# SUPPORT.net
KiCad netlist of a schematic drawn in Altium Designer
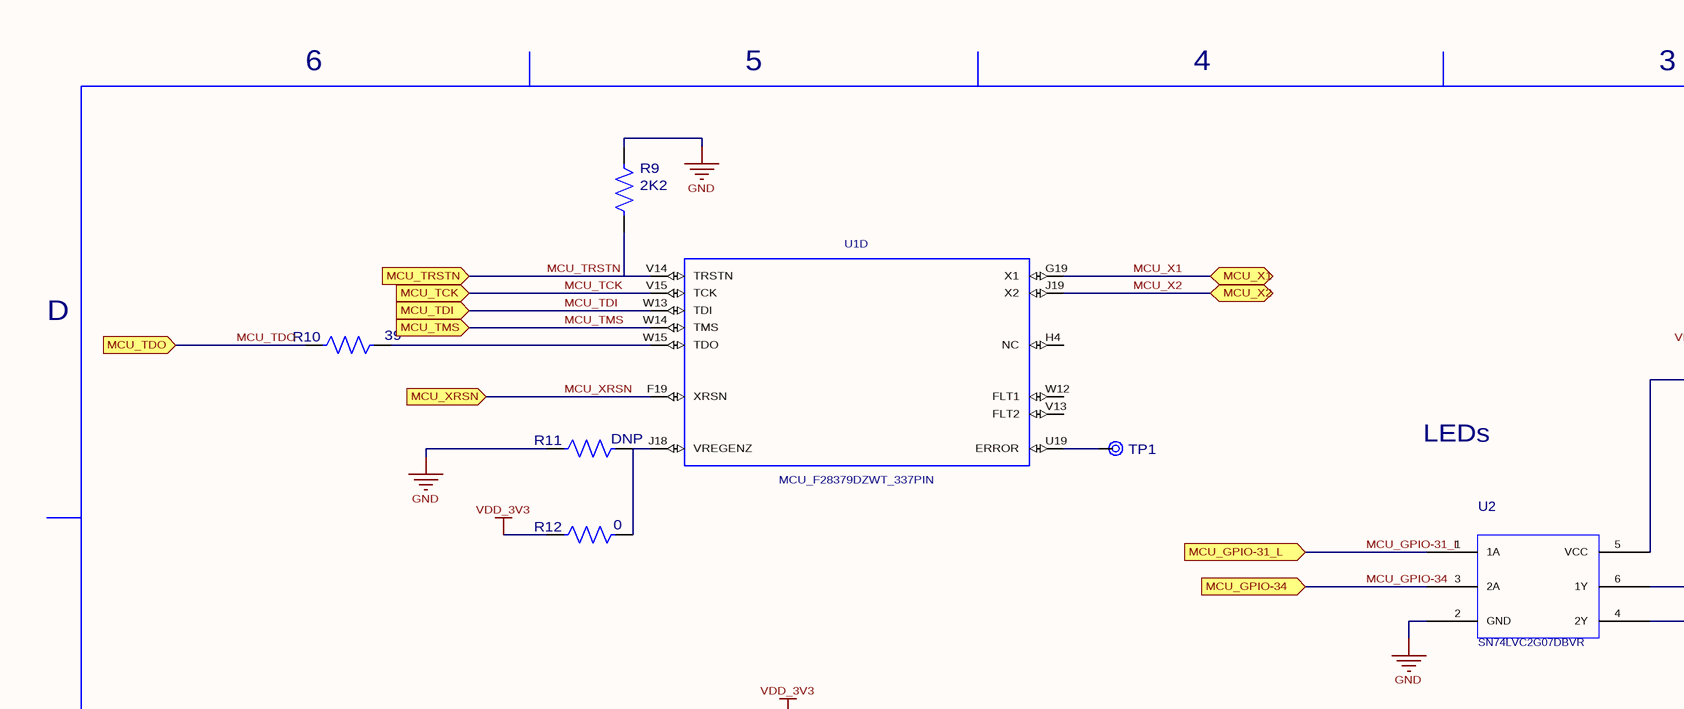
[diagram p0: SUPPORT.SchDoc, top left]
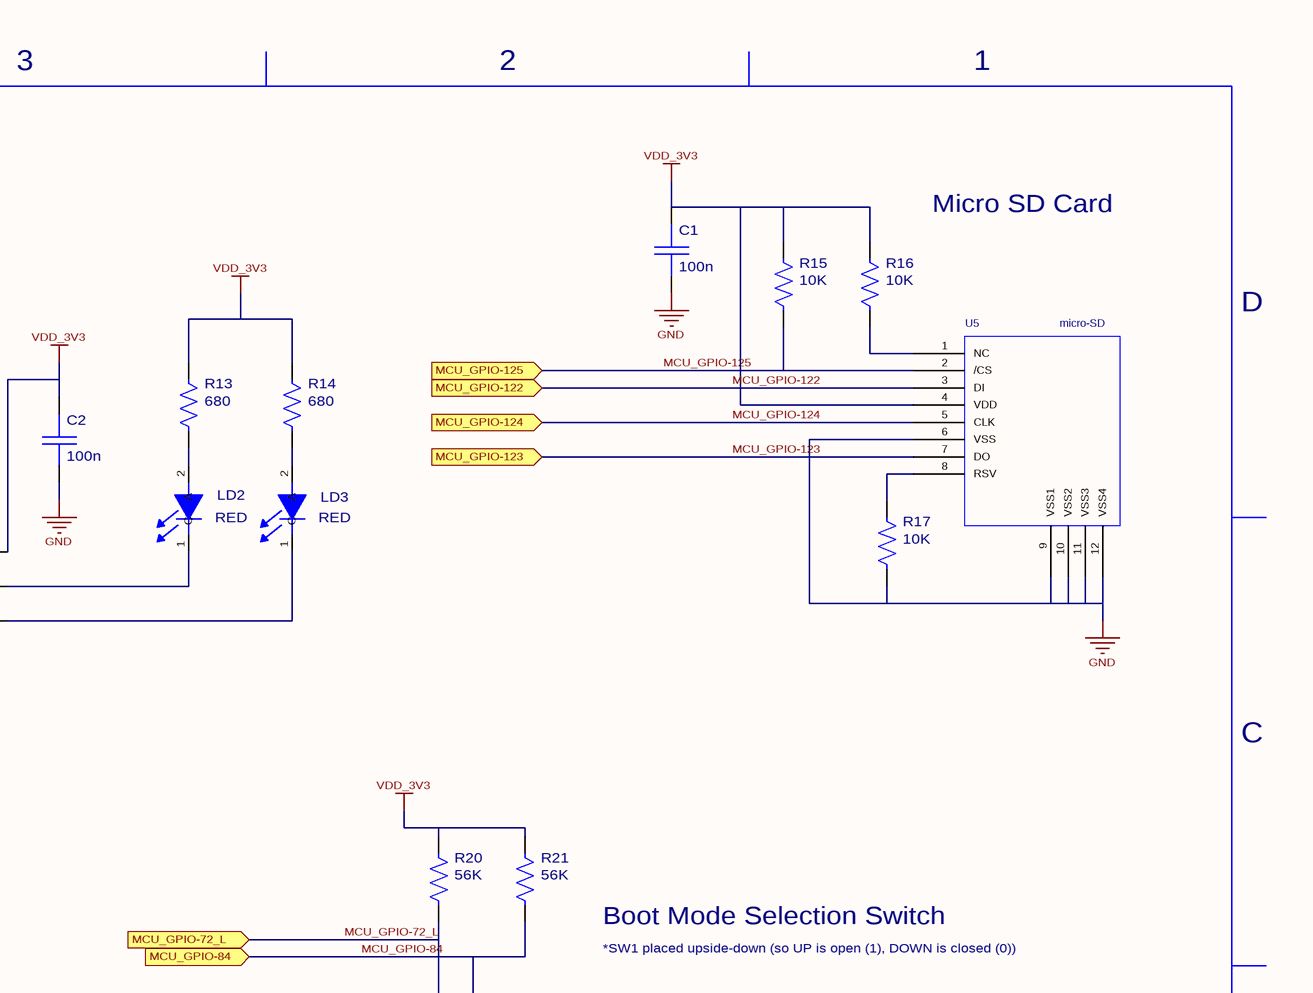
[diagram p1: SUPPORT.SchDoc, top right]
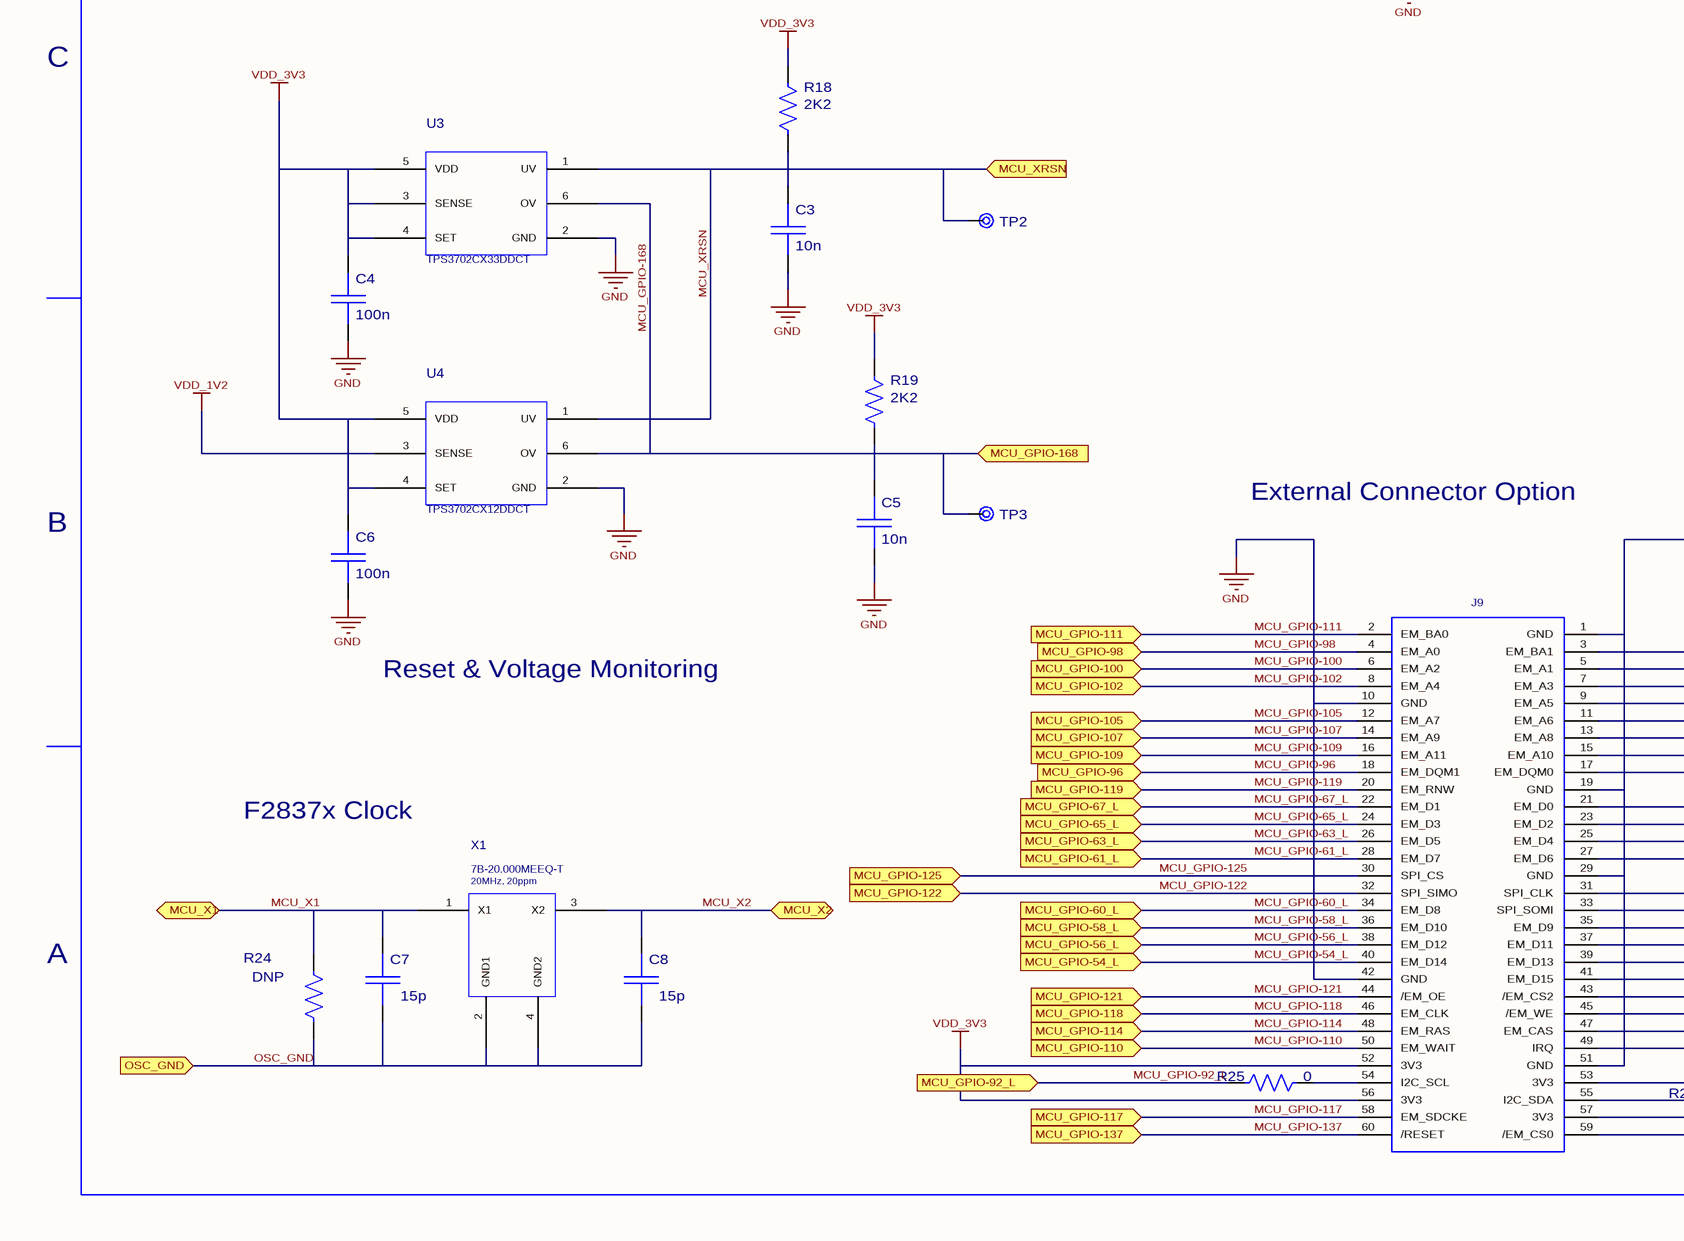
[diagram p2: SUPPORT.SchDoc, bottom left]
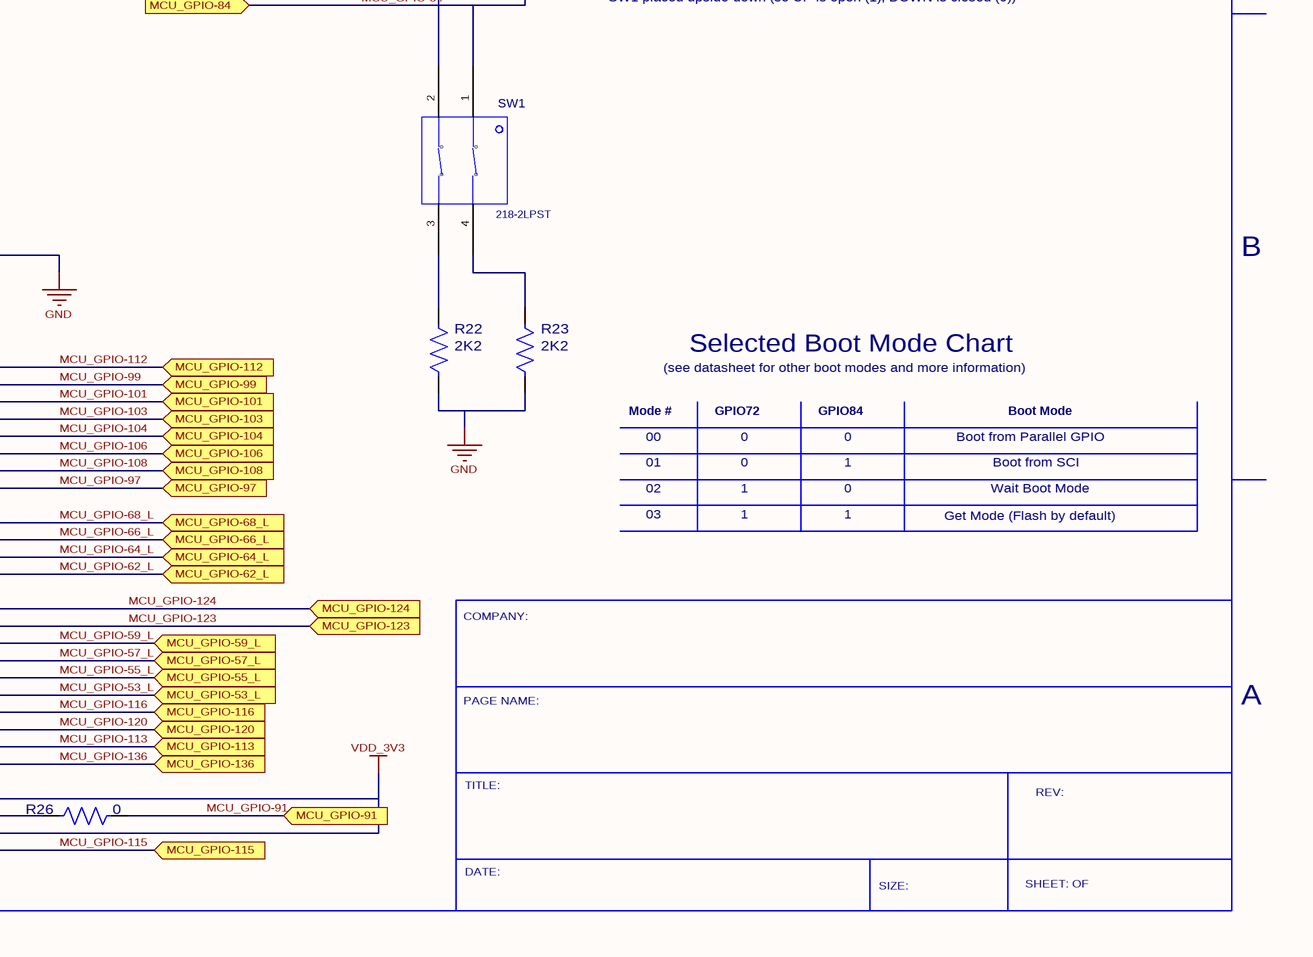
[diagram p3: SUPPORT.SchDoc, bottom right]

(export (version "E")
  (design (tool "Eeschema 10.0.6"))
  (components
    (comp (ref "C1")
      (value "100n")
      (footprint "C0402")
      (description "CAP CER 16V 10% X7R 0402")
      (fields (field (name "Comment") "C0402_16V_X7R"))
      (libsource (lib "*") (part "C0402_16V_X7R"))
    )
    (comp (ref "C2")
      (value "100n")
      (footprint "C0402")
      (description "CAP CER 16V 10% X7R 0402")
      (fields (field (name "Comment") "C0402_16V_X7R"))
      (libsource (lib "*") (part "C0402_16V_X7R"))
    )
    (comp (ref "C3")
      (value "10n")
      (footprint "C0402")
      (description "CAP CER 16V 10% X7R 0402")
      (fields (field (name "Comment") "C0402_16V_X7R"))
      (libsource (lib "*") (part "C0402_16V_X7R"))
    )
    (comp (ref "C4")
      (value "100n")
      (footprint "C0402")
      (description "CAP CER 16V 10% X7R 0402")
      (fields (field (name "Comment") "C0402_16V_X7R"))
      (libsource (lib "*") (part "C0402_16V_X7R"))
    )
    (comp (ref "C5")
      (value "10n")
      (footprint "C0402")
      (description "CAP CER 16V 10% X7R 0402")
      (fields (field (name "Comment") "C0402_16V_X7R"))
      (libsource (lib "*") (part "C0402_16V_X7R"))
    )
    (comp (ref "C6")
      (value "100n")
      (footprint "C0402")
      (description "CAP CER 16V 10% X7R 0402")
      (fields (field (name "Comment") "C0402_16V_X7R"))
      (libsource (lib "*") (part "C0402_16V_X7R"))
    )
    (comp (ref "C7")
      (value "15p")
      (footprint "C0402")
      (description "CAP CER 50V NP0 0402")
      (fields (field (name "Comment") "C0402_50V_NP0"))
      (libsource (lib "*") (part "C0402_50V_NP0"))
    )
    (comp (ref "C8")
      (value "15p")
      (footprint "C0402")
      (description "CAP CER 50V NP0 0402")
      (fields (field (name "Comment") "C0402_50V_NP0"))
      (libsource (lib "*") (part "C0402_50V_NP0"))
    )
    (comp (ref "J9")
      (value "CONN_DF40C_CCARDIF_EMIFANDSPI")
      (footprint "DF40C-60DP-0.4V")
      (description "60pin connector - SMT, Hirose DF40C-60DP-0.4V(51)")
      (fields (field (name "MANUFACTURER") "Hirose") (field (name "PART NUMBER") "DF40C-60DP-0.4V(51)"))
      (libsource (lib "*") (part "CONN_DF40C_CCARDIF_EMIFANDSPI"))
    )
    (comp (ref "LD2")
      (value "RED")
      (footprint "LED0805")
      (description "LED RED 0805 SMD, Diffused, 647nm")
      (fields (field (name "Comment") "LED0805_RED"))
      (libsource (lib "*") (part "LED0805_RED"))
    )
    (comp (ref "LD3")
      (value "RED")
      (footprint "LED0805")
      (description "LED RED 0805 SMD, Diffused, 647nm")
      (fields (field (name "Comment") "LED0805_RED"))
      (libsource (lib "*") (part "LED0805_RED"))
    )
    (comp (ref "R9")
      (value "2K2")
      (footprint "R0402")
      (description "RES 1/16W 5% 0402 SMD")
      (fields (field (name "Comment") "R0402_5%"))
      (libsource (lib "*") (part "R0402_5%"))
    )
    (comp (ref "R10")
      (value "39")
      (footprint "R0402")
      (description "RES 1/16W 5% 0402 SMD")
      (fields (field (name "Comment") "R0402_5%"))
      (libsource (lib "*") (part "R0402_5%"))
    )
    (comp (ref "R11")
      (value "DNP")
      (footprint "R0402")
      (description "RES 1/16W 5% 0402 SMD")
      (fields (field (name "Comment") "R0402_5%"))
      (libsource (lib "*") (part "R0402_5%"))
    )
    (comp (ref "R12")
      (value "0")
      (footprint "R0402")
      (description "RES 1/16W 5% 0402 SMD")
      (fields (field (name "Comment") "R0402_5%"))
      (libsource (lib "*") (part "R0402_5%"))
    )
    (comp (ref "R13")
      (value "680")
      (footprint "R0402")
      (description "RES 1/16W 5% 0402 SMD")
      (fields (field (name "Comment") "R0402_5%"))
      (libsource (lib "*") (part "R0402_5%"))
    )
    (comp (ref "R14")
      (value "680")
      (footprint "R0402")
      (description "RES 1/16W 5% 0402 SMD")
      (fields (field (name "Comment") "R0402_5%"))
      (libsource (lib "*") (part "R0402_5%"))
    )
    (comp (ref "R15")
      (value "10K")
      (footprint "R0402")
      (description "RES 1/16W 5% 0402 SMD")
      (fields (field (name "Comment") "R0402_5%"))
      (libsource (lib "*") (part "R0402_5%"))
    )
    (comp (ref "R16")
      (value "10K")
      (footprint "R0402")
      (description "RES 1/16W 5% 0402 SMD")
      (fields (field (name "Comment") "R0402_5%"))
      (libsource (lib "*") (part "R0402_5%"))
    )
    (comp (ref "R17")
      (value "10K")
      (footprint "R0402")
      (description "RES 1/16W 5% 0402 SMD")
      (fields (field (name "Comment") "R0402_5%"))
      (libsource (lib "*") (part "R0402_5%"))
    )
    (comp (ref "R18")
      (value "2K2")
      (footprint "R0402")
      (description "RES 1/16W 5% 0402 SMD")
      (fields (field (name "Comment") "R0402_5%"))
      (libsource (lib "*") (part "R0402_5%"))
    )
    (comp (ref "R19")
      (value "2K2")
      (footprint "R0603")
      (description "RES 1/10W 1% 0603 SMD")
      (fields (field (name "Comment") "R0603_1%"))
      (libsource (lib "*") (part "R0603_1%"))
    )
    (comp (ref "R20")
      (value "56K")
      (footprint "R0402")
      (description "RES 1/16W 5% 0402 SMD")
      (fields (field (name "Comment") "R0402_5%"))
      (libsource (lib "*") (part "R0402_5%"))
    )
    (comp (ref "R21")
      (value "56K")
      (footprint "R0402")
      (description "RES 1/16W 5% 0402 SMD")
      (fields (field (name "Comment") "R0402_5%"))
      (libsource (lib "*") (part "R0402_5%"))
    )
    (comp (ref "R22")
      (value "2K2")
      (footprint "R0402")
      (description "RES 1/16W 5% 0402 SMD")
      (fields (field (name "Comment") "R0402_5%"))
      (libsource (lib "*") (part "R0402_5%"))
    )
    (comp (ref "R23")
      (value "2K2")
      (footprint "R0402")
      (description "RES 1/16W 5% 0402 SMD")
      (fields (field (name "Comment") "R0402_5%"))
      (libsource (lib "*") (part "R0402_5%"))
    )
    (comp (ref "R24")
      (value "DNP")
      (footprint "R0402")
      (description "RES 1/16W 5% 0402 SMD")
      (fields (field (name "Comment") "R0402_5%"))
      (libsource (lib "*") (part "R0402_5%"))
    )
    (comp (ref "R25")
      (value "0")
      (footprint "R0402")
      (description "RES 1/16W 5% 0402 SMD")
      (fields (field (name "Comment") "R0402_5%"))
      (libsource (lib "*") (part "R0402_5%"))
    )
    (comp (ref "R26")
      (value "0")
      (footprint "R0402")
      (description "RES 1/16W 5% 0402 SMD")
      (fields (field (name "Comment") "R0402_5%"))
      (libsource (lib "*") (part "R0402_5%"))
    )
    (comp (ref "SW1")
      (value "218-2LPST")
      (footprint "SW_2POS_CTS218")
      (description "2xSPST DIP switch SMT, half-pitch")
      (fields
        (field (name "MANUFACTURER") "CTS Electrocomponents")
        (field (name "Comment") "SWITCH_2XSPST_SMT")
      )
      (libsource (lib "*") (part "SWITCH_2XSPST_SMT"))
    )
    (comp (ref "TP1")
      (value "VIA_20_40")
      (footprint "VIA_20_40")
      (description "Via, 20 ID, 40 OD (mil)")
      (libsource (lib "*") (part "VIA_20_40"))
    )
    (comp (ref "TP2")
      (value "VIA_20_40")
      (footprint "VIA_20_40")
      (description "Via, 20 ID, 40 OD (mil)")
      (libsource (lib "*") (part "VIA_20_40"))
    )
    (comp (ref "TP3")
      (value "VIA_20_40")
      (footprint "VIA_20_40")
      (description "Via, 20 ID, 40 OD (mil)")
      (libsource (lib "*") (part "VIA_20_40"))
    )
    (comp (ref "U1")
      (value "MCU_F28379DZWT_337PIN")
      (footprint "TI_ZWT_337BGA")
      (description "MCU F2837x 337pin ZWT BGA")
      (fields (field (name "PART NUMBER") "TMS320F28379DZWT"))
      (libsource (lib "*") (part "MCU_F28379DZWT_337PIN"))
    )
    (comp (ref "U2")
      (value "SN74LVC2G07DBVR")
      (footprint "SOT-23-6")
      (description "Buffer Line Driver, non-inverting, 32mA")
      (fields
        (field (name "MANUFACTURER") "Texas Instruments")
        (field (name "Comment") "IC_LOGIC_SN74LVC2G07DBV")
      )
      (libsource (lib "*") (part "IC_LOGIC_SN74LVC2G07DBV"))
    )
    (comp (ref "U3")
      (value "TPS3702CX33DDCT")
      (footprint "SOT-23-6")
      (description "Volage Monitor, 3.3V, 5% or 10%")
      (fields
        (field (name "MANUFACTURER") "Texas Instruments")
        (field (name "Comment") "IC_SVS_TPS3702CX33DDC")
      )
      (libsource (lib "*") (part "IC_SVS_TPS3702CX33DDC"))
    )
    (comp (ref "U4")
      (value "TPS3702CX12DDCT")
      (footprint "SOT-23-6")
      (description "Volage Monitor, 1.2V, 5% or 10%")
      (fields
        (field (name "MANUFACTURER") "Texas Instruments")
        (field (name "Comment") "IC_SVS_TPS3702CX12DDC")
      )
      (libsource (lib "*") (part "IC_SVS_TPS3702CX12DDC"))
    )
    (comp (ref "U5")
      (value "micro-SD")
      (footprint "CONN_SDMICRO-3M-2900")
      (description "micro SD Connector+Ejector, 10 (8+2) positions, SMT-top")
      (fields (field (name "MANUFACTURER") "3M") (field (name "PART NUMBER") "2908-05WB-MG"))
      (libsource (lib "*") (part "CONN_MICROSD_2908-05WB-MG"))
    )
    (comp (ref "X1")
      (value "20MHz, 20ppm")
      (footprint "XTAL_TXC_7B")
      (description "20MHz Crystal, 20ppm")
      (fields
        (field (name "MANUFACTURER") "TXC Corporation")
        (field (name "PART NUMBER") "7B-20.000MEEQ-T")
        (field (name "Comment") "XTAL_7B-20.000MEEQ-T")
      )
      (libsource (lib "*") (part "XTAL_7B-20.000MEEQ-T"))
    )
  )
  (nets
    (net (code "1") (name "/MCU_GPIO-31_L") (class "Default")
      (node (ref "U2") (pin "1") (pinfunction "1A_1") (pintype "passive"))
    )
    (net (code "2") (name "/MCU_GPIO-34") (class "Default")
      (node (ref "U2") (pin "3") (pinfunction "2A_3") (pintype "passive"))
    )
    (net (code "3") (name "/MCU_GPIO-53_L") (class "Default")
      (node (ref "J9") (pin "41") (pinfunction "EM_D15_41") (pintype "passive"))
    )
    (net (code "4") (name "/MCU_GPIO-54_L") (class "Default")
      (node (ref "J9") (pin "40") (pinfunction "EM_D14_40") (pintype "passive"))
    )
    (net (code "5") (name "/MCU_GPIO-55_L") (class "Default")
      (node (ref "J9") (pin "39") (pinfunction "EM_D13_39") (pintype "passive"))
    )
    (net (code "6") (name "/MCU_GPIO-56_L") (class "Default")
      (node (ref "J9") (pin "38") (pinfunction "EM_D12_38") (pintype "passive"))
    )
    (net (code "7") (name "/MCU_GPIO-57_L") (class "Default")
      (node (ref "J9") (pin "37") (pinfunction "EM_D11_37") (pintype "passive"))
    )
    (net (code "8") (name "/MCU_GPIO-58_L") (class "Default")
      (node (ref "J9") (pin "36") (pinfunction "EM_D10_36") (pintype "passive"))
    )
    (net (code "9") (name "/MCU_GPIO-59_L") (class "Default")
      (node (ref "J9") (pin "35") (pinfunction "EM_D9_35") (pintype "passive"))
    )
    (net (code "10") (name "/MCU_GPIO-60_L") (class "Default")
      (node (ref "J9") (pin "34") (pinfunction "EM_D8_34") (pintype "passive"))
    )
    (net (code "11") (name "/MCU_GPIO-61_L") (class "Default")
      (node (ref "J9") (pin "28") (pinfunction "EM_D7_28") (pintype "passive"))
    )
    (net (code "12") (name "/MCU_GPIO-62_L") (class "Default")
      (node (ref "J9") (pin "27") (pinfunction "EM_D6_27") (pintype "passive"))
    )
    (net (code "13") (name "/MCU_GPIO-63_L") (class "Default")
      (node (ref "J9") (pin "26") (pinfunction "EM_D5_26") (pintype "passive"))
    )
    (net (code "14") (name "/MCU_GPIO-64_L") (class "Default")
      (node (ref "J9") (pin "25") (pinfunction "EM_D4_25") (pintype "passive"))
    )
    (net (code "15") (name "/MCU_GPIO-65_L") (class "Default")
      (node (ref "J9") (pin "24") (pinfunction "EM_D3_24") (pintype "passive"))
    )
    (net (code "16") (name "/MCU_GPIO-66_L") (class "Default")
      (node (ref "J9") (pin "23") (pinfunction "EM_D2_23") (pintype "passive"))
    )
    (net (code "17") (name "/MCU_GPIO-67_L") (class "Default")
      (node (ref "J9") (pin "22") (pinfunction "EM_D1_22") (pintype "passive"))
    )
    (net (code "18") (name "/MCU_GPIO-68_L") (class "Default")
      (node (ref "J9") (pin "21") (pinfunction "EM_D0_21") (pintype "passive"))
    )
    (net (code "19") (name "/MCU_GPIO-72_L") (class "Default")
      (node (ref "R20") (pin "2") (pinfunction "2_2") (pintype "passive"))
      (node (ref "SW1") (pin "2") (pinfunction "B_OUT2_2") (pintype "passive"))
    )
    (net (code "20") (name "/MCU_GPIO-84") (class "Default")
      (node (ref "R21") (pin "2") (pinfunction "2_2") (pintype "passive"))
      (node (ref "SW1") (pin "1") (pinfunction "A_OUT1_1") (pintype "passive"))
    )
    (net (code "21") (name "/MCU_GPIO-91") (class "Default")
      (node (ref "R26") (pin "2") (pinfunction "2_2") (pintype "passive"))
    )
    (net (code "22") (name "/MCU_GPIO-92_L") (class "Default")
      (node (ref "R25") (pin "1") (pinfunction "1_1") (pintype "passive"))
    )
    (net (code "23") (name "/MCU_GPIO-96") (class "Default")
      (node (ref "J9") (pin "18") (pinfunction "EM_DQM1_18") (pintype "passive"))
    )
    (net (code "24") (name "/MCU_GPIO-97") (class "Default")
      (node (ref "J9") (pin "17") (pinfunction "EM_DQM0_17") (pintype "passive"))
    )
    (net (code "25") (name "/MCU_GPIO-98") (class "Default")
      (node (ref "J9") (pin "4") (pinfunction "EM_A0_4") (pintype "passive"))
    )
    (net (code "26") (name "/MCU_GPIO-99") (class "Default")
      (node (ref "J9") (pin "5") (pinfunction "EM_A1_5") (pintype "passive"))
    )
    (net (code "27") (name "/MCU_GPIO-100") (class "Default")
      (node (ref "J9") (pin "6") (pinfunction "EM_A2_6") (pintype "passive"))
    )
    (net (code "28") (name "/MCU_GPIO-101") (class "Default")
      (node (ref "J9") (pin "7") (pinfunction "EM_A3_7") (pintype "passive"))
    )
    (net (code "29") (name "/MCU_GPIO-102") (class "Default")
      (node (ref "J9") (pin "8") (pinfunction "EM_A4_8") (pintype "passive"))
    )
    (net (code "30") (name "/MCU_GPIO-103") (class "Default")
      (node (ref "J9") (pin "9") (pinfunction "EM_A5_9") (pintype "passive"))
    )
    (net (code "31") (name "/MCU_GPIO-104") (class "Default")
      (node (ref "J9") (pin "11") (pinfunction "EM_A6_11") (pintype "passive"))
    )
    (net (code "32") (name "/MCU_GPIO-105") (class "Default")
      (node (ref "J9") (pin "12") (pinfunction "EM_A7_12") (pintype "passive"))
    )
    (net (code "33") (name "/MCU_GPIO-106") (class "Default")
      (node (ref "J9") (pin "13") (pinfunction "EM_A8_13") (pintype "passive"))
    )
    (net (code "34") (name "/MCU_GPIO-107") (class "Default")
      (node (ref "J9") (pin "14") (pinfunction "EM_A9_14") (pintype "passive"))
    )
    (net (code "35") (name "/MCU_GPIO-108") (class "Default")
      (node (ref "J9") (pin "15") (pinfunction "EM_A10_15") (pintype "passive"))
    )
    (net (code "36") (name "/MCU_GPIO-109") (class "Default")
      (node (ref "J9") (pin "16") (pinfunction "EM_A11_16") (pintype "passive"))
    )
    (net (code "37") (name "/MCU_GPIO-110") (class "Default")
      (node (ref "J9") (pin "50") (pinfunction "EM_WAIT_50") (pintype "passive"))
    )
    (net (code "38") (name "/MCU_GPIO-111") (class "Default")
      (node (ref "J9") (pin "2") (pinfunction "EM_BA0_2") (pintype "passive"))
    )
    (net (code "39") (name "/MCU_GPIO-112") (class "Default")
      (node (ref "J9") (pin "3") (pinfunction "EM_BA1_3") (pintype "passive"))
    )
    (net (code "40") (name "/MCU_GPIO-113") (class "Default")
      (node (ref "J9") (pin "47") (pinfunction "EM_CAS_47") (pintype "passive"))
    )
    (net (code "41") (name "/MCU_GPIO-114") (class "Default")
      (node (ref "J9") (pin "48") (pinfunction "EM_RAS_48") (pintype "passive"))
    )
    (net (code "42") (name "/MCU_GPIO-115") (class "Default")
      (node (ref "J9") (pin "59") (pinfunction "/EM_CS0_59") (pintype "passive"))
    )
    (net (code "43") (name "/MCU_GPIO-116") (class "Default")
      (node (ref "J9") (pin "43") (pinfunction "/EM_CS2_43") (pintype "passive"))
    )
    (net (code "44") (name "/MCU_GPIO-117") (class "Default")
      (node (ref "J9") (pin "58") (pinfunction "EM_SDCKE_58") (pintype "passive"))
    )
    (net (code "45") (name "/MCU_GPIO-118") (class "Default")
      (node (ref "J9") (pin "46") (pinfunction "EM_CLK_46") (pintype "passive"))
    )
    (net (code "46") (name "/MCU_GPIO-119") (class "Default")
      (node (ref "J9") (pin "20") (pinfunction "EM_RNW_20") (pintype "passive"))
    )
    (net (code "47") (name "/MCU_GPIO-120") (class "Default")
      (node (ref "J9") (pin "45") (pinfunction "/EM_WE_45") (pintype "passive"))
    )
    (net (code "48") (name "/MCU_GPIO-121") (class "Default")
      (node (ref "J9") (pin "44") (pinfunction "/EM_OE_44") (pintype "passive"))
    )
    (net (code "49") (name "/MCU_GPIO-122") (class "Default")
      (node (ref "J9") (pin "32") (pinfunction "SPI_SIMO_32") (pintype "passive"))
      (node (ref "U5") (pin "3") (pinfunction "DI_3") (pintype "passive"))
    )
    (net (code "50") (name "/MCU_GPIO-123") (class "Default")
      (node (ref "J9") (pin "33") (pinfunction "SPI_SOMI_33") (pintype "passive"))
      (node (ref "U5") (pin "7") (pinfunction "DO_7") (pintype "passive"))
    )
    (net (code "51") (name "/MCU_GPIO-124") (class "Default")
      (node (ref "J9") (pin "31") (pinfunction "SPI_CLK_31") (pintype "passive"))
      (node (ref "U5") (pin "5") (pinfunction "CLK_5") (pintype "passive"))
    )
    (net (code "52") (name "/MCU_GPIO-125") (class "Default")
      (node (ref "J9") (pin "30") (pinfunction "SPI_CS_30") (pintype "passive"))
      (node (ref "R15") (pin "2") (pinfunction "2_2") (pintype "passive"))
      (node (ref "U5") (pin "2") (pinfunction "/CS_2") (pintype "passive"))
    )
    (net (code "53") (name "/MCU_GPIO-136") (class "Default")
      (node (ref "J9") (pin "49") (pinfunction "IRQ_49") (pintype "passive"))
    )
    (net (code "54") (name "/MCU_GPIO-137") (class "Default")
      (node (ref "J9") (pin "60") (pinfunction "/RESET_60") (pintype "passive"))
    )
    (net (code "55") (name "/MCU_GPIO-168") (class "Default")
      (node (ref "C5") (pin "2") (pinfunction "2_2") (pintype "passive"))
      (node (ref "R19") (pin "2") (pinfunction "2_2") (pintype "passive"))
      (node (ref "TP3") (pin "1") (pinfunction "1_1") (pintype "passive"))
      (node (ref "U3") (pin "6") (pinfunction "OV_6") (pintype "passive"))
      (node (ref "U4") (pin "6") (pinfunction "OV_6") (pintype "passive"))
    )
    (net (code "56") (name "/MCU_TCK") (class "Default")
      (node (ref "U1") (pin "V15") (pinfunction "TCK_V15") (pintype "bidirectional"))
    )
    (net (code "57") (name "/MCU_TDI") (class "Default")
      (node (ref "U1") (pin "W13") (pinfunction "TDI_W13") (pintype "bidirectional"))
    )
    (net (code "58") (name "/MCU_TDO") (class "Default")
      (node (ref "R10") (pin "1") (pinfunction "1_1") (pintype "passive"))
    )
    (net (code "59") (name "/MCU_TMS") (class "Default")
      (node (ref "U1") (pin "W14") (pinfunction "TMS_W14") (pintype "bidirectional"))
    )
    (net (code "60") (name "/MCU_TRSTN") (class "Default")
      (node (ref "R9") (pin "2") (pinfunction "2_2") (pintype "passive"))
      (node (ref "U1") (pin "V14") (pinfunction "TRSTN_V14") (pintype "bidirectional"))
    )
    (net (code "61") (name "/MCU_X1") (class "Default")
      (node (ref "C7") (pin "2") (pinfunction "2_2") (pintype "passive"))
      (node (ref "R24") (pin "1") (pinfunction "1_1") (pintype "passive"))
      (node (ref "U1") (pin "G19") (pinfunction "X1_G19") (pintype "bidirectional"))
      (node (ref "X1") (pin "1") (pinfunction "X1_1") (pintype "passive"))
    )
    (net (code "62") (name "/MCU_X2") (class "Default")
      (node (ref "C8") (pin "2") (pinfunction "2_2") (pintype "passive"))
      (node (ref "U1") (pin "J19") (pinfunction "X2_J19") (pintype "bidirectional"))
      (node (ref "X1") (pin "3") (pinfunction "X2_3") (pintype "passive"))
    )
    (net (code "63") (name "/MCU_XRSN") (class "Default")
      (node (ref "C3") (pin "2") (pinfunction "2_2") (pintype "passive"))
      (node (ref "R18") (pin "2") (pinfunction "2_2") (pintype "passive"))
      (node (ref "TP2") (pin "1") (pinfunction "1_1") (pintype "passive"))
      (node (ref "U1") (pin "F19") (pinfunction "XRSN_F19") (pintype "bidirectional"))
      (node (ref "U3") (pin "1") (pinfunction "UV_1") (pintype "power_in"))
      (node (ref "U4") (pin "1") (pinfunction "UV_1") (pintype "power_in"))
    )
    (net (code "64") (name "/OSC_GND") (class "Default")
      (node (ref "C7") (pin "1") (pinfunction "1_1") (pintype "passive"))
      (node (ref "C8") (pin "1") (pinfunction "1_1") (pintype "passive"))
      (node (ref "R24") (pin "2") (pinfunction "2_2") (pintype "passive"))
      (node (ref "X1") (pin "2") (pinfunction "GND1_2") (pintype "passive"))
      (node (ref "X1") (pin "4") (pinfunction "GND2_4") (pintype "passive"))
    )
    (net (code "65") (name "GND") (class "Default")
      (node (ref "C1") (pin "1") (pinfunction "1_1") (pintype "passive"))
      (node (ref "C2") (pin "1") (pinfunction "1_1") (pintype "passive"))
      (node (ref "C3") (pin "1") (pinfunction "1_1") (pintype "passive"))
      (node (ref "C4") (pin "1") (pinfunction "1_1") (pintype "passive"))
      (node (ref "C5") (pin "1") (pinfunction "1_1") (pintype "passive"))
      (node (ref "C6") (pin "1") (pinfunction "1_1") (pintype "passive"))
      (node (ref "J9") (pin "1") (pinfunction "GND_1") (pintype "passive"))
      (node (ref "J9") (pin "10") (pinfunction "GND_10") (pintype "passive"))
      (node (ref "J9") (pin "19") (pinfunction "GND_19") (pintype "passive"))
      (node (ref "J9") (pin "29") (pinfunction "GND_29") (pintype "passive"))
      (node (ref "J9") (pin "42") (pinfunction "GND_42") (pintype "passive"))
      (node (ref "J9") (pin "51") (pinfunction "GND_51") (pintype "passive"))
      (node (ref "R11") (pin "1") (pinfunction "1_1") (pintype "passive"))
      (node (ref "R17") (pin "2") (pinfunction "2_2") (pintype "passive"))
      (node (ref "R22") (pin "2") (pinfunction "2_2") (pintype "passive"))
      (node (ref "R23") (pin "2") (pinfunction "2_2") (pintype "passive"))
      (node (ref "R9") (pin "1") (pinfunction "1_1") (pintype "passive"))
      (node (ref "U2") (pin "2") (pinfunction "GND_2") (pintype "power_in"))
      (node (ref "U3") (pin "2") (pinfunction "GND_2") (pintype "passive"))
      (node (ref "U4") (pin "2") (pinfunction "GND_2") (pintype "passive"))
      (node (ref "U5") (pin "10") (pinfunction "VSS2_10") (pintype "passive"))
      (node (ref "U5") (pin "11") (pinfunction "VSS3_11") (pintype "passive"))
      (node (ref "U5") (pin "12") (pinfunction "VSS4_12") (pintype "passive"))
      (node (ref "U5") (pin "6") (pinfunction "VSS_6") (pintype "passive"))
      (node (ref "U5") (pin "9") (pinfunction "VSS1_9") (pintype "passive"))
    )
    (net (code "66") (name "Net-(J9-I2C_SCL)") (class "Default")
      (node (ref "J9") (pin "54") (pinfunction "I2C_SCL_54") (pintype "passive"))
      (node (ref "R25") (pin "2") (pinfunction "2_2") (pintype "passive"))
    )
    (net (code "67") (name "Net-(J9-I2C_SDA)") (class "Default")
      (node (ref "J9") (pin "55") (pinfunction "I2C_SDA_55") (pintype "passive"))
      (node (ref "R26") (pin "1") (pinfunction "1_1") (pintype "passive"))
    )
    (net (code "68") (name "Net-(LD2-A)") (class "Default")
      (node (ref "LD2") (pin "2") (pinfunction "A_2") (pintype "passive"))
      (node (ref "R13") (pin "2") (pinfunction "2_2") (pintype "passive"))
    )
    (net (code "69") (name "Net-(LD2-C)") (class "Default")
      (node (ref "LD2") (pin "1") (pinfunction "C_1") (pintype "passive"))
      (node (ref "U2") (pin "6") (pinfunction "1Y_6") (pintype "passive"))
    )
    (net (code "70") (name "Net-(LD3-A)") (class "Default")
      (node (ref "LD3") (pin "2") (pinfunction "A_2") (pintype "passive"))
      (node (ref "R14") (pin "2") (pinfunction "2_2") (pintype "passive"))
    )
    (net (code "71") (name "Net-(LD3-C)") (class "Default")
      (node (ref "LD3") (pin "1") (pinfunction "C_1") (pintype "passive"))
      (node (ref "U2") (pin "4") (pinfunction "2Y_4") (pintype "passive"))
    )
    (net (code "72") (name "Net-(SW1-A_IN1)") (class "Default")
      (node (ref "R23") (pin "1") (pinfunction "1_1") (pintype "passive"))
      (node (ref "SW1") (pin "4") (pinfunction "A_IN1_4") (pintype "passive"))
    )
    (net (code "73") (name "Net-(SW1-B_IN1)") (class "Default")
      (node (ref "R22") (pin "1") (pinfunction "1_1") (pintype "passive"))
      (node (ref "SW1") (pin "3") (pinfunction "B_IN1_3") (pintype "passive"))
    )
    (net (code "74") (name "Net-(U1D-ERROR)") (class "Default")
      (node (ref "TP1") (pin "1") (pinfunction "1_1") (pintype "passive"))
      (node (ref "U1") (pin "U19") (pinfunction "ERROR_U19") (pintype "bidirectional"))
    )
    (net (code "75") (name "Net-(U1D-TDO)") (class "Default")
      (node (ref "R10") (pin "2") (pinfunction "2_2") (pintype "passive"))
      (node (ref "U1") (pin "W15") (pinfunction "TDO_W15") (pintype "bidirectional"))
    )
    (net (code "76") (name "Net-(U1D-VREGENZ)") (class "Default")
      (node (ref "R11") (pin "2") (pinfunction "2_2") (pintype "passive"))
      (node (ref "R12") (pin "2") (pinfunction "2_2") (pintype "passive"))
      (node (ref "U1") (pin "J18") (pinfunction "VREGENZ_J18") (pintype "bidirectional"))
    )
    (net (code "77") (name "Net-(U5-NC)") (class "Default")
      (node (ref "R16") (pin "2") (pinfunction "2_2") (pintype "passive"))
      (node (ref "U5") (pin "1") (pinfunction "NC_1") (pintype "passive"))
    )
    (net (code "78") (name "Net-(U5-RSV)") (class "Default")
      (node (ref "R17") (pin "1") (pinfunction "1_1") (pintype "passive"))
      (node (ref "U5") (pin "8") (pinfunction "RSV_8") (pintype "passive"))
    )
    (net (code "79") (name "VDD_1V2") (class "Default")
      (node (ref "U4") (pin "3") (pinfunction "SENSE_3") (pintype "passive"))
    )
    (net (code "80") (name "VDD_3V3") (class "Default")
      (node (ref "C1") (pin "2") (pinfunction "2_2") (pintype "passive"))
      (node (ref "C2") (pin "2") (pinfunction "2_2") (pintype "passive"))
      (node (ref "C4") (pin "2") (pinfunction "2_2") (pintype "passive"))
      (node (ref "C6") (pin "2") (pinfunction "2_2") (pintype "passive"))
      (node (ref "J9") (pin "52") (pinfunction "3V3_52") (pintype "passive"))
      (node (ref "J9") (pin "53") (pinfunction "3V3_53") (pintype "passive"))
      (node (ref "J9") (pin "56") (pinfunction "3V3_56") (pintype "passive"))
      (node (ref "J9") (pin "57") (pinfunction "3V3_57") (pintype "passive"))
      (node (ref "R12") (pin "1") (pinfunction "1_1") (pintype "passive"))
      (node (ref "R13") (pin "1") (pinfunction "1_1") (pintype "passive"))
      (node (ref "R14") (pin "1") (pinfunction "1_1") (pintype "passive"))
      (node (ref "R15") (pin "1") (pinfunction "1_1") (pintype "passive"))
      (node (ref "R16") (pin "1") (pinfunction "1_1") (pintype "passive"))
      (node (ref "R18") (pin "1") (pinfunction "1_1") (pintype "passive"))
      (node (ref "R19") (pin "1") (pinfunction "1_1") (pintype "passive"))
      (node (ref "R20") (pin "1") (pinfunction "1_1") (pintype "passive"))
      (node (ref "R21") (pin "1") (pinfunction "1_1") (pintype "passive"))
      (node (ref "U2") (pin "5") (pinfunction "VCC_5") (pintype "passive"))
      (node (ref "U3") (pin "3") (pinfunction "SENSE_3") (pintype "passive"))
      (node (ref "U3") (pin "4") (pinfunction "SET_4") (pintype "passive"))
      (node (ref "U3") (pin "5") (pinfunction "VDD_5") (pintype "power_in"))
      (node (ref "U4") (pin "4") (pinfunction "SET_4") (pintype "passive"))
      (node (ref "U4") (pin "5") (pinfunction "VDD_5") (pintype "power_in"))
      (node (ref "U5") (pin "4") (pinfunction "VDD_4") (pintype "passive"))
    )
    (net (code "81") (name "unconnected-(U1D-FLT1-PadW12)") (class "Default")
      (node (ref "U1") (pin "W12") (pinfunction "FLT1_W12") (pintype "bidirectional"))
    )
    (net (code "82") (name "unconnected-(U1D-FLT2-PadV13)") (class "Default")
      (node (ref "U1") (pin "V13") (pinfunction "FLT2_V13") (pintype "bidirectional"))
    )
    (net (code "83") (name "unconnected-(U1D-NC-PadH4)") (class "Default")
      (node (ref "U1") (pin "H4") (pinfunction "NC_H4") (pintype "bidirectional"))
    )
  )
)
